# OZ440-SE130-CAR001-SCH3.net
KiCad netlist of a schematic drawn in Altium Designer
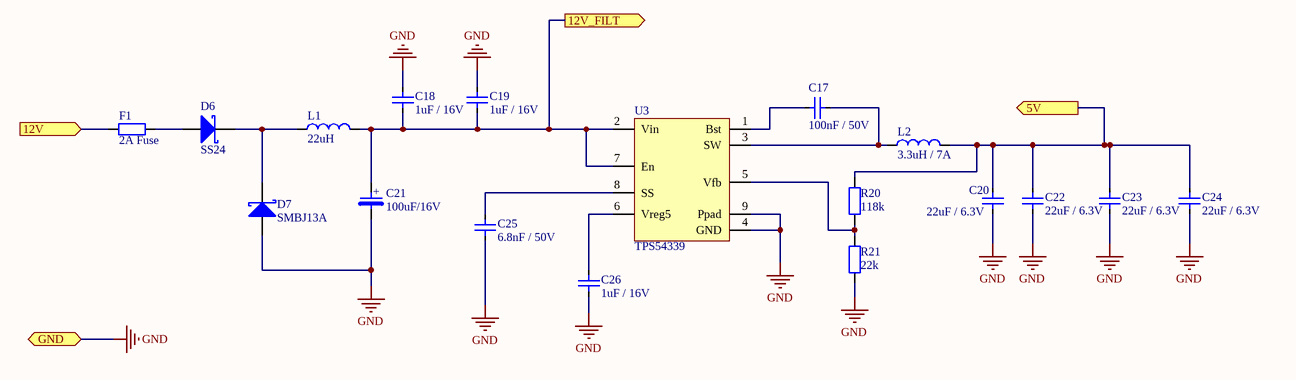
[diagram p0: OZ440-SE130-CAR001-SCH3.SchDoc]

(export (version "E")
  (design (tool "Eeschema 10.0.6"))
  (components
    (comp (ref "C17")
      (value "CAP-SMD")
      (footprint "C0805-STD")
      (description "0805 100nF / 50V  X7R ceramic capacitor")
      (fields
        (field (name "DISPLAYED REFERENCE") "100nF / 50V")
        (field (name "TOLERANCE") "+/- 10%")
        (field (name "MANUFACTURER") "vishay")
      )
      (libsource (lib "lib_NAIO") (part "CAP-SMD"))
    )
    (comp (ref "C18")
      (value "CAP-SMD")
      (footprint "C0805-STD")
      (description "0805 1uF / 16V X7R ceramic capacitor")
      (fields
        (field (name "DISPLAYED REFERENCE") "1uF / 16V")
        (field (name "TOLERANCE") "+/- 10%")
        (field (name "MANUFACTURER") "Kemet")
      )
      (libsource (lib "lib_NAIO") (part "CAP-SMD"))
    )
    (comp (ref "C19")
      (value "CAP-SMD")
      (footprint "C0805-STD")
      (description "0805 1uF / 16V X7R ceramic capacitor")
      (fields
        (field (name "DISPLAYED REFERENCE") "1uF / 16V")
        (field (name "TOLERANCE") "+/- 10%")
        (field (name "MANUFACTURER") "Kemet")
      )
      (libsource (lib "lib_NAIO") (part "CAP-SMD"))
    )
    (comp (ref "C20")
      (value "CAP-SMD")
      (footprint "C0805-STD")
      (description "0805 22uF / 6.3V X5R ceramic capacitor")
      (fields
        (field (name "DISPLAYED REFERENCE") "22uF / 6.3V")
        (field (name "TOLERANCE") "+/- 20%")
        (field (name "MANUFACTURER") "Kemet")
      )
      (libsource (lib "lib_NAIO") (part "CAP-SMD"))
    )
    (comp (ref "C21")
      (value "CAP-POL-SMD")
      (footprint "CAP-ELECTRO-SMD")
      (description "100uF/16V Aluminium capacitor SMD")
      (fields (field (name "DISPLAYED REFERENCE") "100uF/16V") (field (name "MANUFACTURER") "Epcos"))
      (libsource (lib "lib_NAIO") (part "CAP-POL-SMD"))
    )
    (comp (ref "C22")
      (value "CAP-SMD")
      (footprint "C0805-STD")
      (description "0805 22uF / 6.3V X5R ceramic capacitor")
      (fields
        (field (name "DISPLAYED REFERENCE") "22uF / 6.3V")
        (field (name "TOLERANCE") "+/- 20%")
        (field (name "MANUFACTURER") "Kemet")
      )
      (libsource (lib "lib_NAIO") (part "CAP-SMD"))
    )
    (comp (ref "C23")
      (value "CAP-SMD")
      (footprint "C0805-STD")
      (description "0805 22uF / 6.3V X5R ceramic capacitor")
      (fields
        (field (name "DISPLAYED REFERENCE") "22uF / 6.3V")
        (field (name "TOLERANCE") "+/- 20%")
        (field (name "MANUFACTURER") "Kemet")
      )
      (libsource (lib "lib_NAIO") (part "CAP-SMD"))
    )
    (comp (ref "C24")
      (value "CAP-SMD")
      (footprint "C0805-STD")
      (description "0805 22uF / 6.3V X5R ceramic capacitor")
      (fields
        (field (name "DISPLAYED REFERENCE") "22uF / 6.3V")
        (field (name "TOLERANCE") "+/- 20%")
        (field (name "MANUFACTURER") "Kemet")
      )
      (libsource (lib "lib_NAIO") (part "CAP-SMD"))
    )
    (comp (ref "C25")
      (value "CAP-SMD")
      (footprint "C0805-STD")
      (description "0805 6.8nF / 50V COG ceramic capacitor")
      (fields
        (field (name "DISPLAYED REFERENCE") "6.8nF / 50V")
        (field (name "TOLERANCE") "+/- 5%")
        (field (name "MANUFACTURER") "Kemet")
      )
      (libsource (lib "lib_NAIO") (part "CAP-SMD"))
    )
    (comp (ref "C26")
      (value "CAP-SMD")
      (footprint "C0805-STD")
      (description "0805 1uF / 16V X7R ceramic capacitor")
      (fields
        (field (name "DISPLAYED REFERENCE") "1uF / 16V")
        (field (name "TOLERANCE") "+/- 10%")
        (field (name "MANUFACTURER") "Kemet")
      )
      (libsource (lib "lib_NAIO") (part "CAP-SMD"))
    )
    (comp (ref "D6")
      (value "DIODE_SCHOTKY-DO214AA")
      (footprint "DO214AA-STD")
      (description "2A/40V schottky diode in SMB package")
      (fields (field (name "DISPLAYED REFERENCE") "SS24") (field (name "MANUFACTURER") "VISHAY"))
      (libsource (lib "lib_NAIO") (part "DIODE_SCHOTKY-DO214AA"))
    )
    (comp (ref "D7")
      (value "DIODE_SCHOTKY-DO214AA")
      (footprint "DO214AA-STD")
      (description "13V TVS diode, 600W")
      (fields (field (name "DISPLAYED REFERENCE") "SMBJ13A") (field (name "MANUFACTURER") "LITTLEFUSE"))
      (libsource (lib "lib_NAIO") (part "DIODE_SCHOTKY-DO214AA"))
    )
    (comp (ref "F1")
      (value "RES-SMD")
      (footprint "R0805-STD")
      (description "0805 2A 63V fuse")
      (fields (field (name "DISPLAYED REFERENCE") "2A Fuse") (field (name "MANUFACTURER") "AVX"))
      (libsource (lib "") (part "RES-SMD_1"))
    )
    (comp (ref "L1")
      (value "IND-SMD")
      (footprint "L-SPE-LPS6235")
      (description "22uH SMD inductor")
      (fields (field (name "DISPLAYED REFERENCE") "22uH") (field (name "MANUFACTURER") "Coilcraft"))
      (libsource (lib "") (part "IND-SMD_1"))
    )
    (comp (ref "L2")
      (value "IND-SMD")
      (footprint "L-SPE-EPL6024")
      (description "3.3uH 7A SMD inductor")
      (fields (field (name "DISPLAYED REFERENCE") "3.3uH / 7A") (field (name "MANUFACTURER") "COILCRAFT"))
      (libsource (lib "lib_NAIO") (part "IND-SMD"))
    )
    (comp (ref "R20")
      (value "RES-SMD")
      (footprint "R0805-STD")
      (description "118k Ohm 0805 SMD resistor")
      (fields
        (field (name "DISPLAYED REFERENCE") "118k")
        (field (name "TOLERANCE") "1%")
        (field (name "MANUFACTURER") "Vishay")
      )
      (libsource (lib "lib_NAIO") (part "RES-SMD"))
    )
    (comp (ref "R21")
      (value "RES-SMD")
      (footprint "R0805-STD")
      (description "22k Ohm 0805 SMD resistor")
      (fields
        (field (name "DISPLAYED REFERENCE") "22k")
        (field (name "TOLERANCE") "1 %")
        (field (name "MANUFACTURER") "Vishay")
      )
      (libsource (lib "lib_NAIO") (part "RES-SMD"))
    )
    (comp (ref "U3")
      (value "TPS54339-SO8")
      (footprint "SO8_THERMAL-STD")
      (description "4.5 V to 23 V Input, 3-A Step-Down DCDC")
      (fields (field (name "DISPLAYED REFERENCE") "TPS54339") (field (name "MANUFACTURER") "TI"))
      (libsource (lib "lib_NAIO") (part "TPS54339-SO8"))
    )
  )
  (nets
    (net (code "1") (name "/5V") (class "Default")
      (node (ref "C20") (pin "2") (pinfunction "2_2") (pintype "passive"))
      (node (ref "C22") (pin "2") (pinfunction "2_2") (pintype "passive"))
      (node (ref "C23") (pin "2") (pinfunction "2_2") (pintype "passive"))
      (node (ref "C24") (pin "2") (pinfunction "2_2") (pintype "passive"))
      (node (ref "L2") (pin "2") (pinfunction "2_2") (pintype "passive"))
      (node (ref "R20") (pin "2") (pinfunction "2_2") (pintype "passive"))
    )
    (net (code "2") (name "/12V") (class "Default")
      (node (ref "F1") (pin "1") (pinfunction "1_1") (pintype "passive"))
    )
    (net (code "3") (name "/12V_FILT") (class "Default")
      (node (ref "C18") (pin "1") (pinfunction "1_1") (pintype "passive"))
      (node (ref "C19") (pin "1") (pinfunction "1_1") (pintype "passive"))
      (node (ref "C21") (pin "1") (pinfunction "1_1") (pintype "passive"))
      (node (ref "L1") (pin "2") (pinfunction "2_2") (pintype "passive"))
      (node (ref "U3") (pin "2") (pinfunction "Vin_2") (pintype "passive"))
      (node (ref "U3") (pin "7") (pinfunction "En_7") (pintype "passive"))
    )
    (net (code "4") (name "GND") (class "Default")
      (node (ref "C18") (pin "2") (pinfunction "2_2") (pintype "passive"))
      (node (ref "C19") (pin "2") (pinfunction "2_2") (pintype "passive"))
      (node (ref "C20") (pin "1") (pinfunction "1_1") (pintype "passive"))
      (node (ref "C21") (pin "2") (pinfunction "2_2") (pintype "passive"))
      (node (ref "C22") (pin "1") (pinfunction "1_1") (pintype "passive"))
      (node (ref "C23") (pin "1") (pinfunction "1_1") (pintype "passive"))
      (node (ref "C24") (pin "1") (pinfunction "1_1") (pintype "passive"))
      (node (ref "C25") (pin "1") (pinfunction "1_1") (pintype "passive"))
      (node (ref "C26") (pin "1") (pinfunction "1_1") (pintype "passive"))
      (node (ref "D7") (pin "A") (pinfunction "A_A") (pintype "passive"))
      (node (ref "R21") (pin "1") (pinfunction "1_1") (pintype "passive"))
      (node (ref "U3") (pin "4") (pinfunction "GND_4") (pintype "passive"))
      (node (ref "U3") (pin "9") (pinfunction "Ppad_9") (pintype "passive"))
    )
    (net (code "5") (name "Net-(D6-PadA)") (class "Default")
      (node (ref "D6") (pin "A") (pinfunction "A_A") (pintype "passive"))
      (node (ref "F1") (pin "2") (pinfunction "2_2") (pintype "passive"))
    )
    (net (code "6") (name "Net-(D6-PadK)") (class "Default")
      (node (ref "D6") (pin "K") (pinfunction "K_K") (pintype "passive"))
      (node (ref "D7") (pin "K") (pinfunction "K_K") (pintype "passive"))
      (node (ref "L1") (pin "1") (pinfunction "1_1") (pintype "passive"))
    )
    (net (code "7") (name "Net-(U3-Bst)") (class "Default")
      (node (ref "C17") (pin "1") (pinfunction "1_1") (pintype "passive"))
      (node (ref "U3") (pin "1") (pinfunction "Bst_1") (pintype "passive"))
    )
    (net (code "8") (name "Net-(U3-SS)") (class "Default")
      (node (ref "C25") (pin "2") (pinfunction "2_2") (pintype "passive"))
      (node (ref "U3") (pin "8") (pinfunction "SS_8") (pintype "passive"))
    )
    (net (code "9") (name "Net-(U3-SW)") (class "Default")
      (node (ref "C17") (pin "2") (pinfunction "2_2") (pintype "passive"))
      (node (ref "L2") (pin "1") (pinfunction "1_1") (pintype "passive"))
      (node (ref "U3") (pin "3") (pinfunction "SW_3") (pintype "passive"))
    )
    (net (code "10") (name "Net-(U3-Vfb)") (class "Default")
      (node (ref "R20") (pin "1") (pinfunction "1_1") (pintype "passive"))
      (node (ref "R21") (pin "2") (pinfunction "2_2") (pintype "passive"))
      (node (ref "U3") (pin "5") (pinfunction "Vfb_5") (pintype "passive"))
    )
    (net (code "11") (name "Net-(U3-Vreg5)") (class "Default")
      (node (ref "C26") (pin "2") (pinfunction "2_2") (pintype "passive"))
      (node (ref "U3") (pin "6") (pinfunction "Vreg5_6") (pintype "passive"))
    )
  )
)
